# esp32-expander_2026-01-10.net
KiCad netlist of a schematic drawn in EasyEDA Pro
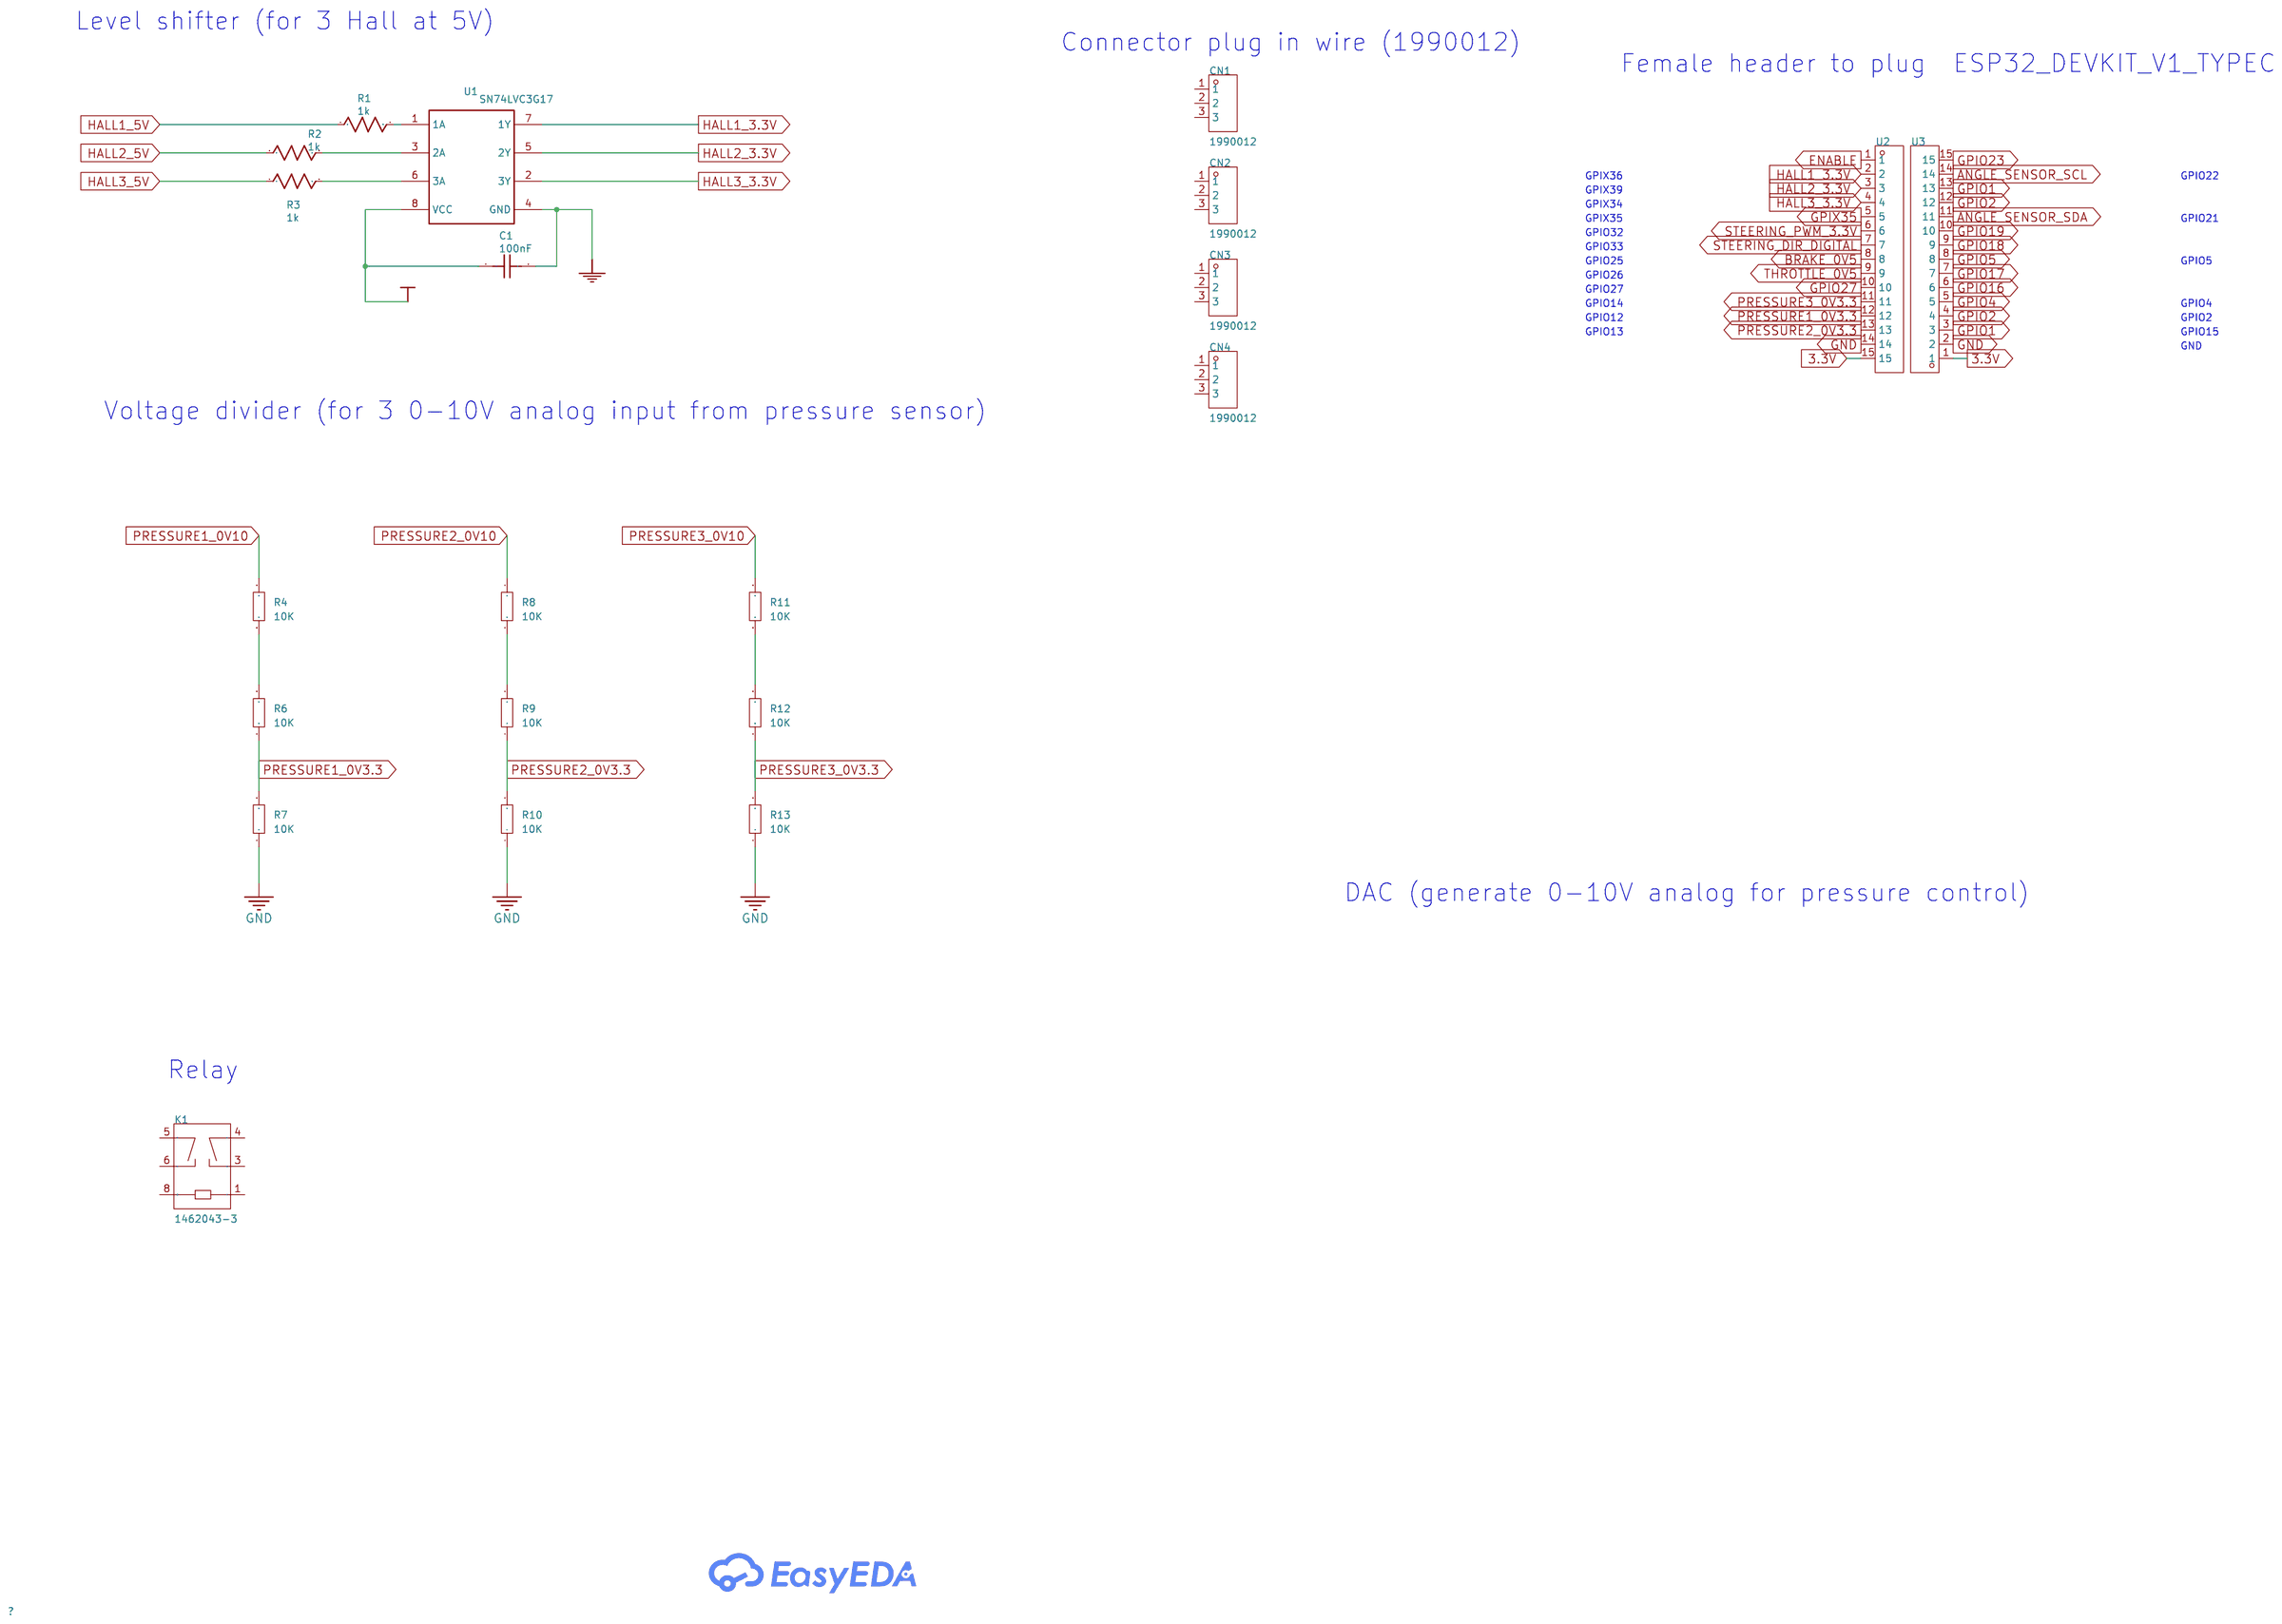
[diagram p0: schematic sheet]

(export (version "E")
  (design (tool "Eeschema 10.0.6"))
  (components
    (comp (ref "C1")
      (value "100nF")
      (footprint "easyedapro:C0603")
      (fields (field (name "Contributor") "LCEDA_Lib"))
      (libsource (lib "easyedapro") (part "100nF"))
    )
    (comp (ref "CN1")
      (value "1990012")
      (footprint "easyedapro:CONN-TH_3P-P2.50-S5.00_1990012")
      (libsource (lib "easyedapro") (part "1990012"))
    )
    (comp (ref "CN2")
      (value "1990012")
      (footprint "easyedapro:CONN-TH_3P-P2.50-S5.00_1990012")
      (libsource (lib "easyedapro") (part "1990012"))
    )
    (comp (ref "CN3")
      (value "1990012")
      (footprint "easyedapro:CONN-TH_3P-P2.50-S5.00_1990012")
      (libsource (lib "easyedapro") (part "1990012"))
    )
    (comp (ref "CN4")
      (value "1990012")
      (footprint "easyedapro:CONN-TH_3P-P2.50-S5.00_1990012")
      (libsource (lib "easyedapro") (part "1990012"))
    )
    (comp (ref "K1")
      (value "1462043-3")
      (footprint "easyedapro:RELAY-SMD_1462043-3")
      (fields (field (name "Manufacturer") "TE Connectivity(泰科电子)"))
      (libsource (lib "easyedapro") (part "1462043-3"))
    )
    (comp (ref "R1")
      (value "1k")
      (footprint "easyedapro:R0603")
      (fields (field (name "Contributor") "LCEDA_Lib"))
      (libsource (lib "easyedapro") (part "1k"))
    )
    (comp (ref "R2")
      (value "1k")
      (footprint "easyedapro:R0603")
      (fields (field (name "Contributor") "LCEDA_Lib"))
      (libsource (lib "easyedapro") (part "1k"))
    )
    (comp (ref "R3")
      (value "1k")
      (footprint "easyedapro:R0603")
      (fields (field (name "Contributor") "LCEDA_Lib"))
      (libsource (lib "easyedapro") (part "1k"))
    )
    (comp (ref "R4") (value "10K") (footprint "easyedapro:R0603") (libsource (lib "easyedapro") (part "Res")))
    (comp (ref "R6") (value "10K") (footprint "easyedapro:R0603") (libsource (lib "easyedapro") (part "Res")))
    (comp (ref "R7") (value "10K") (footprint "easyedapro:R0603") (libsource (lib "easyedapro") (part "Res")))
    (comp (ref "R8") (value "10K") (footprint "easyedapro:R0603") (libsource (lib "easyedapro") (part "Res")))
    (comp (ref "R9") (value "10K") (footprint "easyedapro:R0603") (libsource (lib "easyedapro") (part "Res")))
    (comp (ref "R10")
      (value "10K")
      (footprint "easyedapro:R0603")
      (libsource (lib "easyedapro") (part "Res"))
    )
    (comp (ref "R11")
      (value "10K")
      (footprint "easyedapro:R0603")
      (libsource (lib "easyedapro") (part "Res"))
    )
    (comp (ref "R12")
      (value "10K")
      (footprint "easyedapro:R0603")
      (libsource (lib "easyedapro") (part "Res"))
    )
    (comp (ref "R13")
      (value "10K")
      (footprint "easyedapro:R0603")
      (libsource (lib "easyedapro") (part "Res"))
    )
    (comp (ref "U1")
      (value "SN74LVC3G17")
      (footprint "easyedapro:VSSOP-8_L3.0-W3.0-P0.65-LS5.0-BL")
      (fields
        (field (name "Manufacturer Part") "SN74LVC3G17DCUR")
        (field (name "Manufacturer") "Texas Instruments")
        (field (name "Contributor") "bradyriddle")
      )
      (libsource (lib "easyedapro") (part "SN74LVC3G17"))
    )
    (comp (ref "U2")
      (value "ZX-PM2.54-1-15PY")
      (footprint "easyedapro:HDR-TH_15P-P2.54-V-F")
      (fields (field (name "Manufacturer") "Megastar(兆星)"))
      (libsource (lib "easyedapro") (part "ZX-PM2.54-1-15PY"))
    )
    (comp (ref "U3")
      (value "ZX-PM2.54-1-15PY")
      (footprint "easyedapro:HDR-TH_15P-P2.54-V-F")
      (fields (field (name "Manufacturer") "Megastar(兆星)"))
      (libsource (lib "easyedapro") (part "ZX-PM2.54-1-15PY"))
    )
  )
  (nets
    (net (code "1") (name "+3.3V") (class "Default")
      (node (ref "C1") (pin "1") (pinfunction "1_1") (pintype "unspecified"))
      (node (ref "U1") (pin "8") (pinfunction "VCC_8") (pintype "unspecified"))
    )
    (net (code "2") (name "3.3V") (class "Default")
      (node (ref "U2") (pin "15") (pinfunction "15_15") (pintype "unspecified"))
      (node (ref "U3") (pin "1") (pinfunction "1_1") (pintype "unspecified"))
    )
    (net (code "3") (name "ANGLE_SENSOR_SCL") (class "Default")
      (node (ref "U3") (pin "14") (pinfunction "14_14") (pintype "unspecified"))
    )
    (net (code "4") (name "ANGLE_SENSOR_SDA") (class "Default")
      (node (ref "U3") (pin "11") (pinfunction "11_11") (pintype "unspecified"))
    )
    (net (code "5") (name "BRAKE_0V5") (class "Default")
      (node (ref "U2") (pin "8") (pinfunction "8_8") (pintype "unspecified"))
    )
    (net (code "6") (name "ENABLE") (class "Default")
      (node (ref "U2") (pin "1") (pinfunction "1_1") (pintype "unspecified"))
    )
    (net (code "7") (name "GND") (class "Default")
      (node (ref "C1") (pin "2") (pinfunction "2_2") (pintype "unspecified"))
      (node (ref "R10") (pin "1") (pinfunction "1_1") (pintype "input"))
      (node (ref "R13") (pin "1") (pinfunction "1_1") (pintype "input"))
      (node (ref "R7") (pin "1") (pinfunction "1_1") (pintype "input"))
      (node (ref "U1") (pin "4") (pinfunction "GND_4") (pintype "unspecified"))
      (node (ref "U2") (pin "14") (pinfunction "14_14") (pintype "unspecified"))
      (node (ref "U3") (pin "2") (pinfunction "2_2") (pintype "unspecified"))
    )
    (net (code "8") (name "GPIO1") (class "Default")
      (node (ref "U3") (pin "13") (pinfunction "13_13") (pintype "unspecified"))
      (node (ref "U3") (pin "3") (pinfunction "3_3") (pintype "unspecified"))
    )
    (net (code "9") (name "GPIO2") (class "Default")
      (node (ref "U3") (pin "12") (pinfunction "12_12") (pintype "unspecified"))
      (node (ref "U3") (pin "4") (pinfunction "4_4") (pintype "unspecified"))
    )
    (net (code "10") (name "GPIO4") (class "Default")
      (node (ref "U3") (pin "5") (pinfunction "5_5") (pintype "unspecified"))
    )
    (net (code "11") (name "GPIO5") (class "Default")
      (node (ref "U3") (pin "8") (pinfunction "8_8") (pintype "unspecified"))
    )
    (net (code "12") (name "GPIO16") (class "Default")
      (node (ref "U3") (pin "6") (pinfunction "6_6") (pintype "unspecified"))
    )
    (net (code "13") (name "GPIO17") (class "Default")
      (node (ref "U3") (pin "7") (pinfunction "7_7") (pintype "unspecified"))
    )
    (net (code "14") (name "GPIO18") (class "Default")
      (node (ref "U3") (pin "9") (pinfunction "9_9") (pintype "unspecified"))
    )
    (net (code "15") (name "GPIO19") (class "Default")
      (node (ref "U3") (pin "10") (pinfunction "10_10") (pintype "unspecified"))
    )
    (net (code "16") (name "GPIO23") (class "Default")
      (node (ref "U3") (pin "15") (pinfunction "15_15") (pintype "unspecified"))
    )
    (net (code "17") (name "GPIO27") (class "Default")
      (node (ref "U2") (pin "10") (pinfunction "10_10") (pintype "unspecified"))
    )
    (net (code "18") (name "GPIX35") (class "Default")
      (node (ref "U2") (pin "5") (pinfunction "5_5") (pintype "unspecified"))
    )
    (net (code "19") (name "HALL1_3.3V") (class "Default")
      (node (ref "U1") (pin "7") (pinfunction "1Y_7") (pintype "unspecified"))
      (node (ref "U2") (pin "2") (pinfunction "2_2") (pintype "unspecified"))
    )
    (net (code "20") (name "HALL1_5V") (class "Default")
      (node (ref "R1") (pin "1") (pinfunction "1_1") (pintype "unspecified"))
    )
    (net (code "21") (name "HALL2_3.3V") (class "Default")
      (node (ref "U1") (pin "5") (pinfunction "2Y_5") (pintype "unspecified"))
      (node (ref "U2") (pin "3") (pinfunction "3_3") (pintype "unspecified"))
    )
    (net (code "22") (name "HALL2_5V") (class "Default")
      (node (ref "R2") (pin "1") (pinfunction "1_1") (pintype "unspecified"))
    )
    (net (code "23") (name "HALL3_3.3V") (class "Default")
      (node (ref "U1") (pin "2") (pinfunction "3Y_2") (pintype "unspecified"))
      (node (ref "U2") (pin "4") (pinfunction "4_4") (pintype "unspecified"))
    )
    (net (code "24") (name "HALL3_5V") (class "Default")
      (node (ref "R3") (pin "1") (pinfunction "1_1") (pintype "unspecified"))
    )
    (net (code "25") (name "Net-(R4-Pad2)") (class "Default")
      (node (ref "R4") (pin "2") (pinfunction "2_2") (pintype "input"))
      (node (ref "R6") (pin "2") (pinfunction "2_2") (pintype "input"))
    )
    (net (code "26") (name "Net-(R8-Pad2)") (class "Default")
      (node (ref "R8") (pin "2") (pinfunction "2_2") (pintype "input"))
      (node (ref "R9") (pin "2") (pinfunction "2_2") (pintype "input"))
    )
    (net (code "27") (name "Net-(R11-Pad2)") (class "Default")
      (node (ref "R11") (pin "2") (pinfunction "2_2") (pintype "input"))
      (node (ref "R12") (pin "2") (pinfunction "2_2") (pintype "input"))
    )
    (net (code "28") (name "Net-(U1-1A)") (class "Default")
      (node (ref "R1") (pin "2") (pinfunction "2_2") (pintype "unspecified"))
      (node (ref "U1") (pin "1") (pinfunction "1A_1") (pintype "unspecified"))
    )
    (net (code "29") (name "Net-(U1-2A)") (class "Default")
      (node (ref "R2") (pin "2") (pinfunction "2_2") (pintype "unspecified"))
      (node (ref "U1") (pin "3") (pinfunction "2A_3") (pintype "unspecified"))
    )
    (net (code "30") (name "Net-(U1-3A)") (class "Default")
      (node (ref "R3") (pin "2") (pinfunction "2_2") (pintype "unspecified"))
      (node (ref "U1") (pin "6") (pinfunction "3A_6") (pintype "unspecified"))
    )
    (net (code "31") (name "PRESSURE1_0V3.3") (class "Default")
      (node (ref "R6") (pin "1") (pinfunction "1_1") (pintype "input"))
      (node (ref "R7") (pin "2") (pinfunction "2_2") (pintype "input"))
      (node (ref "U2") (pin "12") (pinfunction "12_12") (pintype "unspecified"))
    )
    (net (code "32") (name "PRESSURE1_0V10") (class "Default")
      (node (ref "R4") (pin "1") (pinfunction "1_1") (pintype "input"))
    )
    (net (code "33") (name "PRESSURE2_0V3.3") (class "Default")
      (node (ref "R10") (pin "2") (pinfunction "2_2") (pintype "input"))
      (node (ref "R9") (pin "1") (pinfunction "1_1") (pintype "input"))
      (node (ref "U2") (pin "13") (pinfunction "13_13") (pintype "unspecified"))
    )
    (net (code "34") (name "PRESSURE2_0V10") (class "Default")
      (node (ref "R8") (pin "1") (pinfunction "1_1") (pintype "input"))
    )
    (net (code "35") (name "PRESSURE3_0V3.3") (class "Default")
      (node (ref "R12") (pin "1") (pinfunction "1_1") (pintype "input"))
      (node (ref "R13") (pin "2") (pinfunction "2_2") (pintype "input"))
      (node (ref "U2") (pin "11") (pinfunction "11_11") (pintype "unspecified"))
    )
    (net (code "36") (name "PRESSURE3_0V10") (class "Default")
      (node (ref "R11") (pin "1") (pinfunction "1_1") (pintype "input"))
    )
    (net (code "37") (name "STEERING_DIR_DIGITAL") (class "Default")
      (node (ref "U2") (pin "7") (pinfunction "7_7") (pintype "unspecified"))
    )
    (net (code "38") (name "STEERING_PWM_3.3V") (class "Default")
      (node (ref "U2") (pin "6") (pinfunction "6_6") (pintype "unspecified"))
    )
    (net (code "39") (name "THROTTLE_0V5") (class "Default")
      (node (ref "U2") (pin "9") (pinfunction "9_9") (pintype "unspecified"))
    )
    (net (code "40") (name "unconnected-(CN1-Pad1)") (class "Default")
      (node (ref "CN1") (pin "1") (pinfunction "1_1") (pintype "unspecified"))
    )
    (net (code "41") (name "unconnected-(CN1-Pad2)") (class "Default")
      (node (ref "CN1") (pin "2") (pinfunction "2_2") (pintype "unspecified"))
    )
    (net (code "42") (name "unconnected-(CN1-Pad3)") (class "Default")
      (node (ref "CN1") (pin "3") (pinfunction "3_3") (pintype "unspecified"))
    )
    (net (code "43") (name "unconnected-(CN2-Pad1)") (class "Default")
      (node (ref "CN2") (pin "1") (pinfunction "1_1") (pintype "unspecified"))
    )
    (net (code "44") (name "unconnected-(CN2-Pad2)") (class "Default")
      (node (ref "CN2") (pin "2") (pinfunction "2_2") (pintype "unspecified"))
    )
    (net (code "45") (name "unconnected-(CN2-Pad3)") (class "Default")
      (node (ref "CN2") (pin "3") (pinfunction "3_3") (pintype "unspecified"))
    )
    (net (code "46") (name "unconnected-(CN3-Pad1)") (class "Default")
      (node (ref "CN3") (pin "1") (pinfunction "1_1") (pintype "unspecified"))
    )
    (net (code "47") (name "unconnected-(CN3-Pad2)") (class "Default")
      (node (ref "CN3") (pin "2") (pinfunction "2_2") (pintype "unspecified"))
    )
    (net (code "48") (name "unconnected-(CN3-Pad3)") (class "Default")
      (node (ref "CN3") (pin "3") (pinfunction "3_3") (pintype "unspecified"))
    )
    (net (code "49") (name "unconnected-(CN4-Pad1)") (class "Default")
      (node (ref "CN4") (pin "1") (pinfunction "1_1") (pintype "unspecified"))
    )
    (net (code "50") (name "unconnected-(CN4-Pad2)") (class "Default")
      (node (ref "CN4") (pin "2") (pinfunction "2_2") (pintype "unspecified"))
    )
    (net (code "51") (name "unconnected-(CN4-Pad3)") (class "Default")
      (node (ref "CN4") (pin "3") (pinfunction "3_3") (pintype "unspecified"))
    )
    (net (code "52") (name "unconnected-(K1-Pad1)") (class "Default")
      (node (ref "K1") (pin "1") (pinfunction "1_1") (pintype "unspecified"))
    )
    (net (code "53") (name "unconnected-(K1-Pad3)") (class "Default")
      (node (ref "K1") (pin "3") (pinfunction "3_3") (pintype "unspecified"))
    )
    (net (code "54") (name "unconnected-(K1-Pad4)") (class "Default")
      (node (ref "K1") (pin "4") (pinfunction "4_4") (pintype "unspecified"))
    )
    (net (code "55") (name "unconnected-(K1-Pad5)") (class "Default")
      (node (ref "K1") (pin "5") (pinfunction "5_5") (pintype "unspecified"))
    )
    (net (code "56") (name "unconnected-(K1-Pad6)") (class "Default")
      (node (ref "K1") (pin "6") (pinfunction "6_6") (pintype "unspecified"))
    )
    (net (code "57") (name "unconnected-(K1-Pad8)") (class "Default")
      (node (ref "K1") (pin "8") (pinfunction "8_8") (pintype "unspecified"))
    )
  )
)
